# Adafruit_AS7341.net
KiCad netlist of a schematic drawn in EAGLE
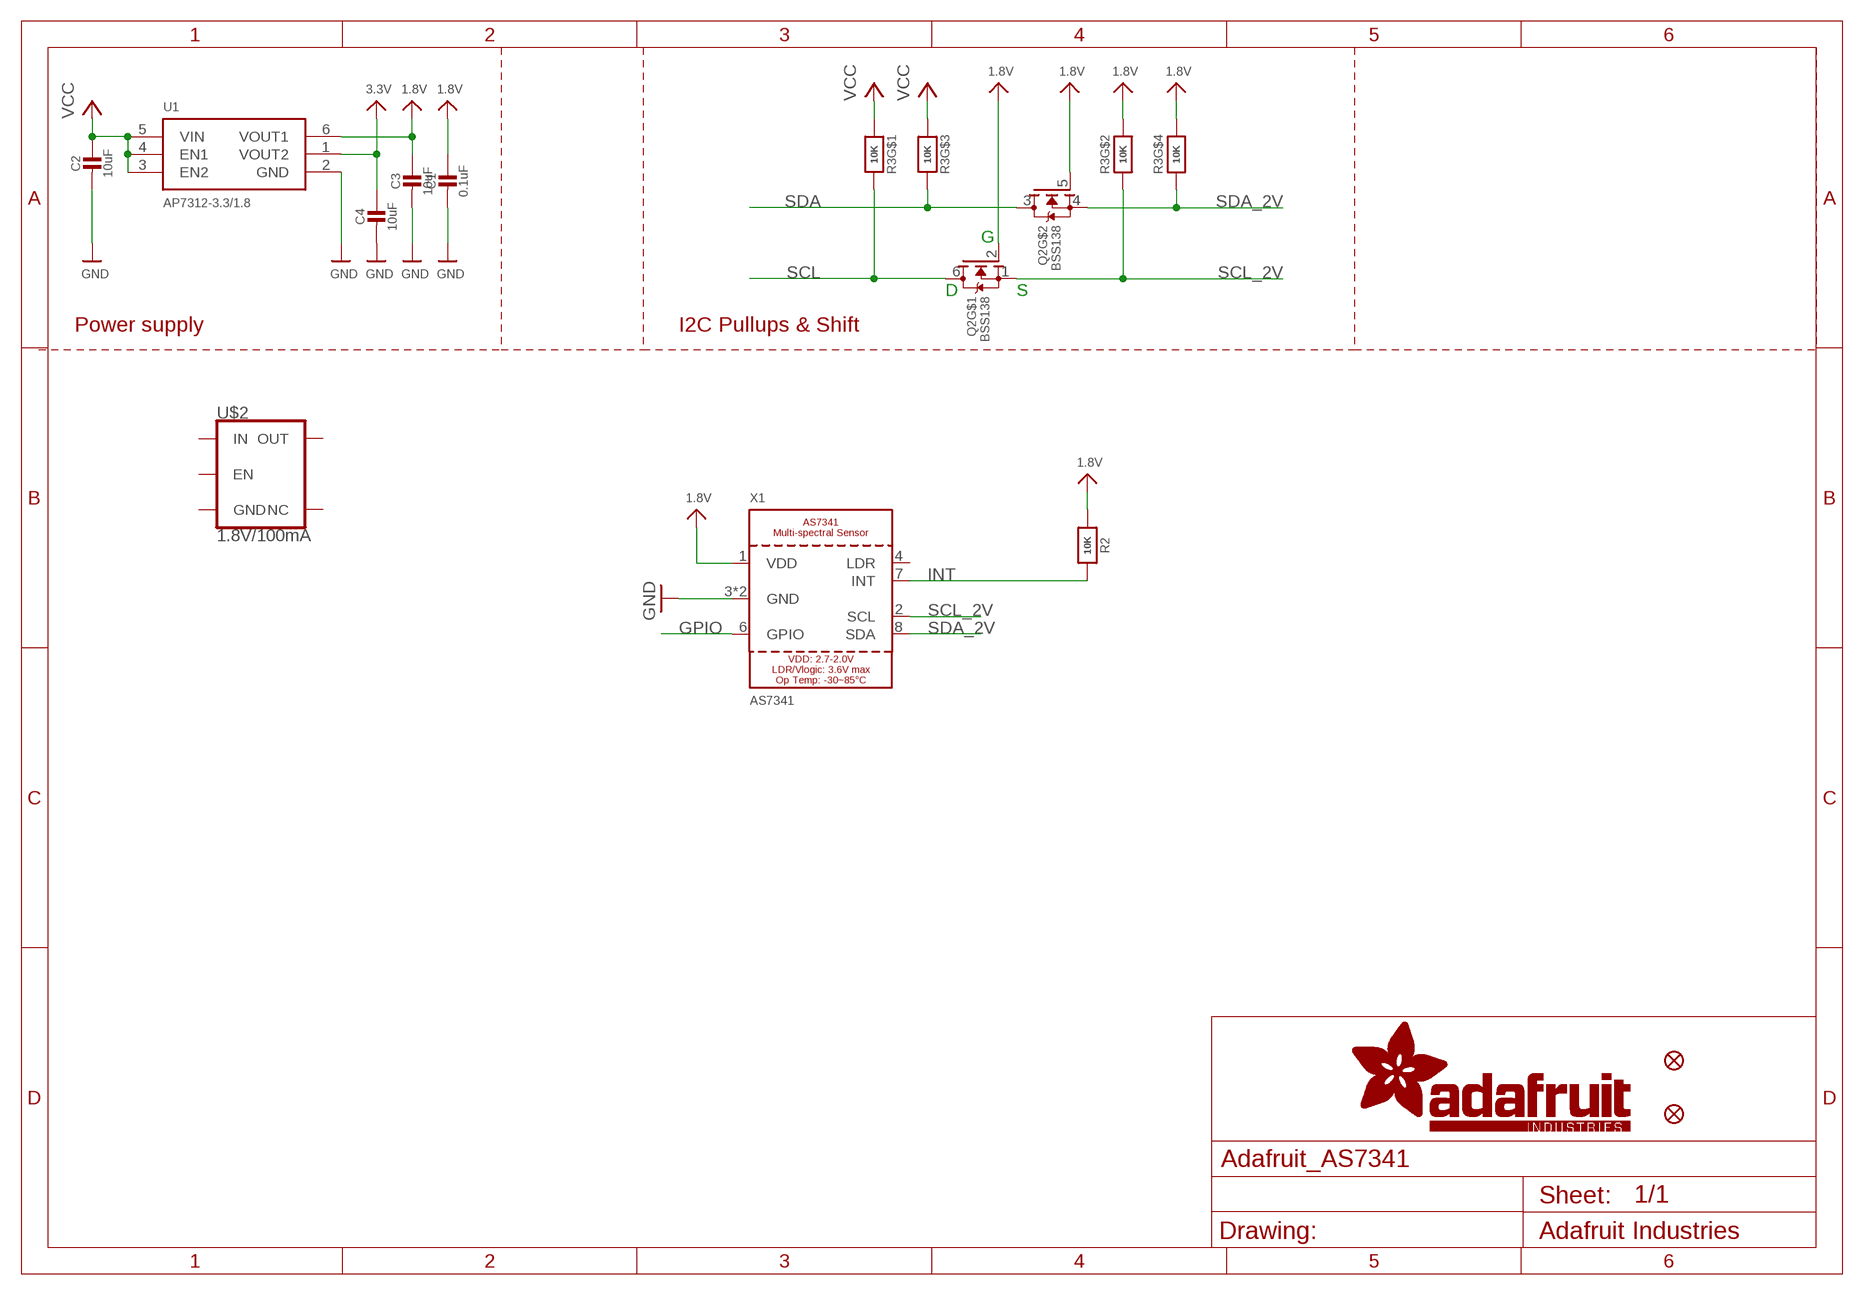
[diagram p0: schematic, sheet 1]

(export (version "E")
  (design (tool "Eeschema 10.0.6"))
  (components
    (comp (ref "C1")
      (value "0.1uF")
      (footprint "eagle-import:0603-NO")
      (libsource (lib "eagle-import") (part "CAP_CERAMIC0603_NO"))
    )
    (comp (ref "C2")
      (value "10uF")
      (footprint "eagle-import:0805-NO")
      (libsource (lib "eagle-import") (part "CAP_CERAMIC0805-NOOUTLINE"))
    )
    (comp (ref "C3")
      (value "10uF")
      (footprint "eagle-import:0805-NO")
      (libsource (lib "eagle-import") (part "CAP_CERAMIC0805-NOOUTLINE"))
    )
    (comp (ref "C4")
      (value "10uF")
      (footprint "eagle-import:0805-NO")
      (libsource (lib "eagle-import") (part "CAP_CERAMIC0805-NOOUTLINE"))
    )
    (comp (ref "FID3")
      (value "FIDUCIAL_1MM")
      (footprint "eagle-import:FIDUCIAL_1MM")
      (libsource (lib "eagle-import") (part "FIDUCIAL_1MM"))
    )
    (comp (ref "FID4")
      (value "FIDUCIAL_1MM")
      (footprint "eagle-import:FIDUCIAL_1MM")
      (libsource (lib "eagle-import") (part "FIDUCIAL_1MM"))
    )
    (comp (ref "Q2")
      (value "BSS138")
      (footprint "eagle-import:SOT363")
      (libsource (lib "eagle-import") (part "MOSFET-N_DUAL"))
    )
    (comp (ref "R2")
      (value "10K")
      (footprint "eagle-import:0603-NO")
      (libsource (lib "eagle-import") (part "RESISTOR_0603_NOOUT"))
    )
    (comp (ref "R3")
      (value "10K")
      (footprint "eagle-import:RESPACK_4X0603")
      (libsource (lib "eagle-import") (part "RESISTOR_4PACK"))
    )
    (comp (ref "U$2")
      (value "1.8V/100mA")
      (footprint "eagle-import:SC70")
      (libsource (lib "eagle-import") (part "V_REG_SP6214-1.8V"))
    )
    (comp (ref "U1")
      (value "AP7312-3.3/1.8")
      (footprint "eagle-import:SOT23-6")
      (libsource (lib "eagle-import") (part "VREG_SOT23-6_DUALAP7312"))
    )
    (comp (ref "X1")
      (value "AS7341")
      (footprint "eagle-import:AS7341")
      (libsource (lib "eagle-import") (part "AS7341"))
    )
  )
  (nets
    (net (code "1") (name "/GPIO") (class "Default")
      (node (ref "X1") (pin "6") (pinfunction "GPIO_6") (pintype "power_in"))
    )
    (net (code "2") (name "/INT") (class "Default")
      (node (ref "R2") (pin "2") (pinfunction "2_2") (pintype "passive"))
      (node (ref "X1") (pin "7") (pinfunction "INT_7") (pintype "output"))
    )
    (net (code "3") (name "/SCL") (class "Default")
      (node (ref "Q2") (pin "6") (pinfunction "D_6") (pintype "bidirectional"))
      (node (ref "R3") (pin "8") (pinfunction "2_8") (pintype "passive"))
    )
    (net (code "4") (name "/SCL_2V") (class "Default")
      (node (ref "Q2") (pin "1") (pinfunction "S_1") (pintype "bidirectional"))
      (node (ref "R3") (pin "7") (pinfunction "2_7") (pintype "passive"))
      (node (ref "X1") (pin "2") (pinfunction "SCL_2") (pintype "input"))
    )
    (net (code "5") (name "/SDA") (class "Default")
      (node (ref "Q2") (pin "3") (pinfunction "D_3") (pintype "bidirectional"))
      (node (ref "R3") (pin "6") (pinfunction "2_6") (pintype "passive"))
    )
    (net (code "6") (name "/SDA_2V") (class "Default")
      (node (ref "Q2") (pin "4") (pinfunction "S_4") (pintype "bidirectional"))
      (node (ref "R3") (pin "5") (pinfunction "2_5") (pintype "passive"))
      (node (ref "X1") (pin "8") (pinfunction "SDA_8") (pintype "bidirectional"))
    )
    (net (code "7") (name "1.8V") (class "Default")
      (node (ref "C1") (pin "1") (pinfunction "1_1") (pintype "passive"))
      (node (ref "C3") (pin "1") (pinfunction "1_1") (pintype "passive"))
      (node (ref "Q2") (pin "2") (pinfunction "G_2") (pintype "bidirectional"))
      (node (ref "Q2") (pin "5") (pinfunction "G_5") (pintype "bidirectional"))
      (node (ref "R2") (pin "1") (pinfunction "1_1") (pintype "passive"))
      (node (ref "R3") (pin "2") (pinfunction "1_2") (pintype "passive"))
      (node (ref "R3") (pin "4") (pinfunction "1_4") (pintype "passive"))
      (node (ref "U1") (pin "6") (pinfunction "VOUT1_6") (pintype "bidirectional"))
      (node (ref "X1") (pin "1") (pinfunction "VDD_1") (pintype "power_in"))
    )
    (net (code "8") (name "3.3V") (class "Default")
      (node (ref "C4") (pin "1") (pinfunction "1_1") (pintype "passive"))
      (node (ref "U1") (pin "1") (pinfunction "VOUT2_1") (pintype "bidirectional"))
    )
    (net (code "9") (name "GND") (class "Default")
      (node (ref "C1") (pin "2") (pinfunction "2_2") (pintype "passive"))
      (node (ref "C2") (pin "2") (pinfunction "2_2") (pintype "passive"))
      (node (ref "C3") (pin "2") (pinfunction "2_2") (pintype "passive"))
      (node (ref "C4") (pin "2") (pinfunction "2_2") (pintype "passive"))
      (node (ref "U1") (pin "2") (pinfunction "GND_2") (pintype "bidirectional"))
      (node (ref "X1") (pin "3") (pinfunction "GND_3") (pintype "power_in"))
      (node (ref "X1") (pin "5") (pinfunction "GND_5") (pintype "power_in"))
    )
    (net (code "10") (name "VCC") (class "Default")
      (node (ref "C2") (pin "1") (pinfunction "1_1") (pintype "passive"))
      (node (ref "R3") (pin "1") (pinfunction "1_1") (pintype "passive"))
      (node (ref "R3") (pin "3") (pinfunction "1_3") (pintype "passive"))
      (node (ref "U1") (pin "3") (pinfunction "EN2_3") (pintype "bidirectional"))
      (node (ref "U1") (pin "4") (pinfunction "EN1_4") (pintype "bidirectional"))
      (node (ref "U1") (pin "5") (pinfunction "VIN_5") (pintype "bidirectional"))
    )
    (net (code "11") (name "unconnected-(U$2-EN-Pad3)") (class "Default")
      (node (ref "U$2") (pin "3") (pinfunction "EN_3") (pintype "input"))
    )
    (net (code "12") (name "unconnected-(U$2-GND-Pad2)") (class "Default")
      (node (ref "U$2") (pin "2") (pinfunction "GND_2") (pintype "input"))
    )
    (net (code "13") (name "unconnected-(U$2-IN-Pad1)") (class "Default")
      (node (ref "U$2") (pin "1") (pinfunction "IN_1") (pintype "input"))
    )
    (net (code "14") (name "unconnected-(U$2-NC-Pad4)") (class "Default")
      (node (ref "U$2") (pin "4") (pinfunction "NC_4") (pintype "no_connect"))
    )
    (net (code "15") (name "unconnected-(U$2-OUT-Pad5)") (class "Default")
      (node (ref "U$2") (pin "5") (pinfunction "OUT_5") (pintype "passive"))
    )
    (net (code "16") (name "unconnected-(X1-LDR-Pad4)") (class "Default")
      (node (ref "X1") (pin "4") (pinfunction "LDR_4") (pintype "bidirectional"))
    )
  )
)
